# AmpSSM2019_2312.net
KiCad netlist of a schematic drawn in EAGLE
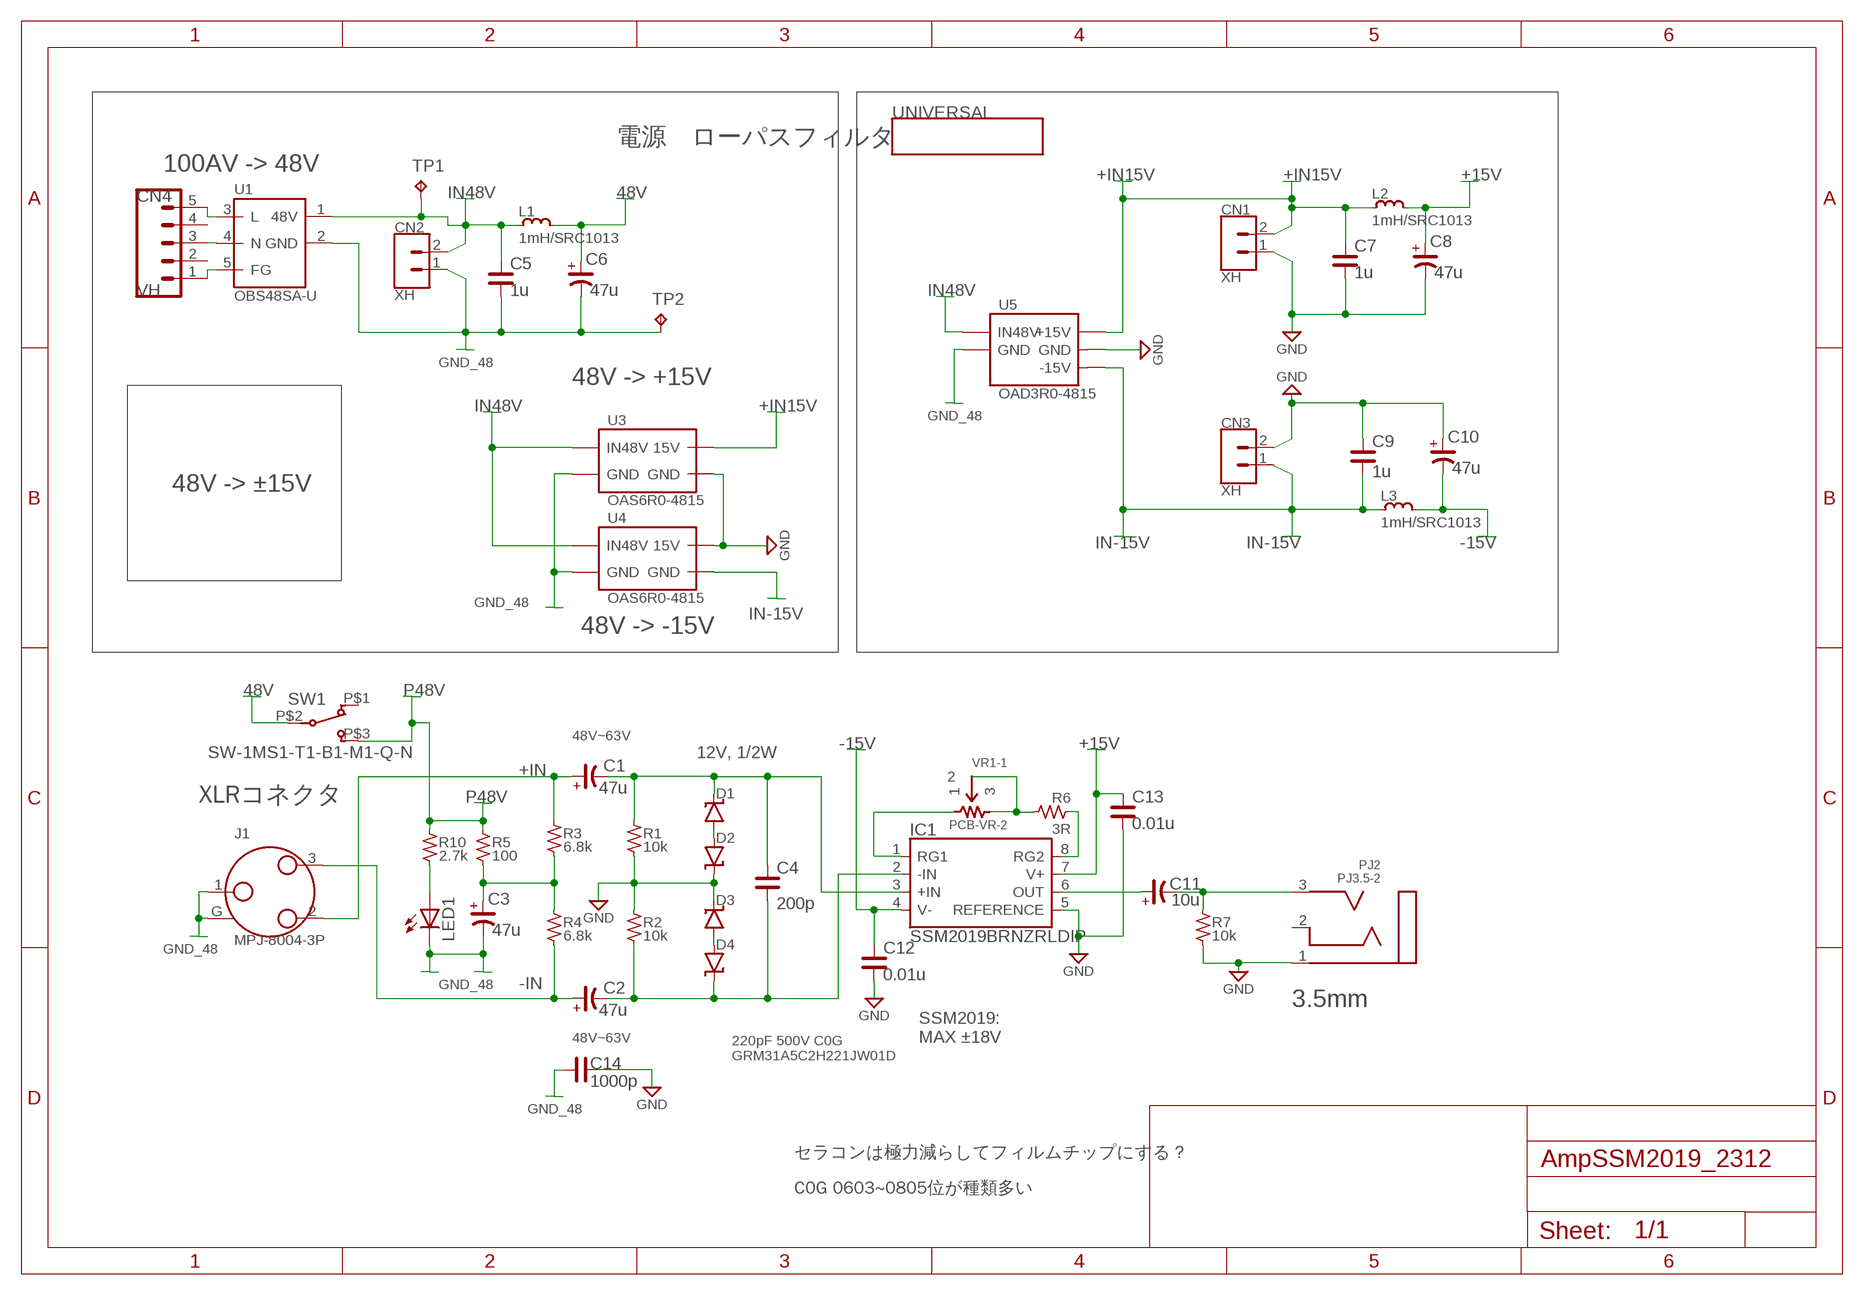
[diagram p0: schematic, sheet 1]

(export (version "E")
  (design (tool "Eeschema 10.0.6"))
  (components
    (comp (ref "C1")
      (value "47u")
      (footprint "eagle-import:CE-025X065")
      (libsource (lib "eagle-import") (part "CP_C025X065"))
    )
    (comp (ref "C2")
      (value "47u")
      (footprint "eagle-import:CE-025X065")
      (libsource (lib "eagle-import") (part "CP_C025X065"))
    )
    (comp (ref "C3")
      (value "47u")
      (footprint "eagle-import:CE-025X065")
      (libsource (lib "eagle-import") (part "CP_C025X065"))
    )
    (comp (ref "C4")
      (value "200p")
      (footprint "eagle-import:C1206")
      (libsource (lib "eagle-import") (part "C_1206"))
    )
    (comp (ref "C5")
      (value "1u")
      (footprint "eagle-import:C1206")
      (libsource (lib "eagle-import") (part "C_1206"))
    )
    (comp (ref "C6")
      (value "47u")
      (footprint "eagle-import:CE-025X065")
      (libsource (lib "eagle-import") (part "CP_C025X065"))
    )
    (comp (ref "C7")
      (value "1u")
      (footprint "eagle-import:C1206")
      (libsource (lib "eagle-import") (part "C_1206"))
    )
    (comp (ref "C8")
      (value "47u")
      (footprint "eagle-import:CE-025X065")
      (libsource (lib "eagle-import") (part "CP_C025X065"))
    )
    (comp (ref "C9")
      (value "1u")
      (footprint "eagle-import:C1206")
      (libsource (lib "eagle-import") (part "C_1206"))
    )
    (comp (ref "C10")
      (value "47u")
      (footprint "eagle-import:CE-025X065")
      (libsource (lib "eagle-import") (part "CP_C025X065"))
    )
    (comp (ref "C11")
      (value "10u")
      (footprint "eagle-import:CE-025X065")
      (libsource (lib "eagle-import") (part "CP_C025X065"))
    )
    (comp (ref "C12")
      (value "0.01u")
      (footprint "eagle-import:C0603")
      (libsource (lib "eagle-import") (part "C_0603"))
    )
    (comp (ref "C13")
      (value "0.01u")
      (footprint "eagle-import:C0603")
      (libsource (lib "eagle-import") (part "C_0603"))
    )
    (comp (ref "C14")
      (value "1000p")
      (footprint "eagle-import:C1206")
      (libsource (lib "eagle-import") (part "C_1206"))
    )
    (comp (ref "CN1")
      (value "XH")
      (footprint "eagle-import:B2B-XH-A")
      (libsource (lib "eagle-import") (part "CN-B2B-XH-A"))
    )
    (comp (ref "CN2")
      (value "XH")
      (footprint "eagle-import:B2B-XH-A")
      (libsource (lib "eagle-import") (part "CN-B2B-XH-A"))
    )
    (comp (ref "CN3")
      (value "XH")
      (footprint "eagle-import:B2B-XH-A")
      (libsource (lib "eagle-import") (part "CN-B2B-XH-A"))
    )
    (comp (ref "CN4")
      (value "VH")
      (footprint "eagle-import:VH5")
      (libsource (lib "eagle-import") (part "M05VH"))
    )
    (comp (ref "D1")
      (value "ZD323")
      (footprint "eagle-import:SOD-323")
      (libsource (lib "eagle-import") (part "ZD323"))
    )
    (comp (ref "D2")
      (value "ZD323")
      (footprint "eagle-import:SOD-323")
      (libsource (lib "eagle-import") (part "ZD323"))
    )
    (comp (ref "D3")
      (value "ZD323")
      (footprint "eagle-import:SOD-323")
      (libsource (lib "eagle-import") (part "ZD323"))
    )
    (comp (ref "D4")
      (value "ZD323")
      (footprint "eagle-import:SOD-323")
      (libsource (lib "eagle-import") (part "ZD323"))
    )
    (comp (ref "IC1")
      (value "SSM2019BRNZRLDIP")
      (footprint "eagle-import:DIL08")
      (libsource (lib "eagle-import") (part "SSM2019BRNZRLDIP"))
    )
    (comp (ref "J1")
      (value "MPJ-8004-3P")
      (footprint "eagle-import:MPJ-8004-3P")
      (libsource (lib "eagle-import") (part "MPJ-8004-3P"))
    )
    (comp (ref "L1")
      (value "1mH/SRC1013")
      (footprint "eagle-import:L13X15")
      (libsource (lib "eagle-import") (part "L_13X15"))
    )
    (comp (ref "L2")
      (value "1mH/SRC1013")
      (footprint "eagle-import:L13X15")
      (libsource (lib "eagle-import") (part "L_13X15"))
    )
    (comp (ref "L3")
      (value "1mH/SRC1013")
      (footprint "eagle-import:L13X15")
      (libsource (lib "eagle-import") (part "L_13X15"))
    )
    (comp (ref "LED1")
      (value "LED3MM")
      (footprint "eagle-import:LED3MM")
      (libsource (lib "eagle-import") (part "LED3MM"))
    )
    (comp (ref "PJ2")
      (value "PJ3.5-2")
      (footprint "eagle-import:PJ3.5-2")
      (libsource (lib "eagle-import") (part "PJ3.5-2"))
    )
    (comp (ref "R1")
      (value "10k")
      (footprint "eagle-import:R0603")
      (libsource (lib "eagle-import") (part "R_0603"))
    )
    (comp (ref "R2")
      (value "10k")
      (footprint "eagle-import:R0603")
      (libsource (lib "eagle-import") (part "R_0603"))
    )
    (comp (ref "R3")
      (value "6.8k")
      (footprint "eagle-import:R0603")
      (libsource (lib "eagle-import") (part "R_0603"))
    )
    (comp (ref "R4")
      (value "6.8k")
      (footprint "eagle-import:R0603")
      (libsource (lib "eagle-import") (part "R_0603"))
    )
    (comp (ref "R5")
      (value "100")
      (footprint "eagle-import:R0603")
      (libsource (lib "eagle-import") (part "R_0603"))
    )
    (comp (ref "R6")
      (value "3R")
      (footprint "eagle-import:R0603")
      (libsource (lib "eagle-import") (part "R_0603"))
    )
    (comp (ref "R7")
      (value "10k")
      (footprint "eagle-import:R0603")
      (libsource (lib "eagle-import") (part "R_0603"))
    )
    (comp (ref "R10")
      (value "2.7k")
      (footprint "eagle-import:R0603")
      (libsource (lib "eagle-import") (part "R_0603"))
    )
    (comp (ref "SW1")
      (value "SW-1MS1-T1-B1-M1-Q-N")
      (footprint "eagle-import:1MS1-T1-B1-M1-Q-N")
      (libsource (lib "eagle-import") (part "SW-1MS1-T1-B1-M1-Q-N"))
    )
    (comp (ref "TP1")
      (value "TPPAD1-13")
      (footprint "eagle-import:P1-13")
      (libsource (lib "eagle-import") (part "TPPAD1-13"))
    )
    (comp (ref "TP2")
      (value "TPPAD1-13")
      (footprint "eagle-import:P1-13")
      (libsource (lib "eagle-import") (part "TPPAD1-13"))
    )
    (comp (ref "U1")
      (value "OBS48SA-U")
      (footprint "eagle-import:OBS48SA-U")
      (libsource (lib "eagle-import") (part "OBS48SA-U"))
    )
    (comp (ref "U2")
      (value "UNIVERSAL10X10")
      (footprint "eagle-import:UNIVERSAL10X10")
      (libsource (lib "eagle-import") (part "UNIVERSAL10X10"))
    )
    (comp (ref "U3")
      (value "OAS6R0-4815")
      (footprint "eagle-import:OAS6R0-4815")
      (libsource (lib "eagle-import") (part "OAS6R0-4815"))
    )
    (comp (ref "U4")
      (value "OAS6R0-4815")
      (footprint "eagle-import:OAS6R0-4815")
      (libsource (lib "eagle-import") (part "OAS6R0-4815"))
    )
    (comp (ref "U5")
      (value "OAD3R0-4815")
      (footprint "eagle-import:OAD3R0-4815")
      (libsource (lib "eagle-import") (part "OAD3R0-4815"))
    )
    (comp (ref "VR1")
      (value "PCB-VR-2")
      (footprint "eagle-import:PCB-VR-2")
      (libsource (lib "eagle-import") (part "PCB-VR-2"))
    )
  )
  (nets
    (net (code "1") (name "/+15V") (class "Default")
      (node (ref "C13") (pin "2") (pinfunction "2_2") (pintype "passive"))
      (node (ref "C8") (pin "+") (pinfunction "+_+") (pintype "passive"))
      (node (ref "IC1") (pin "7") (pinfunction "V+_7") (pintype "bidirectional"))
      (node (ref "L2") (pin "2") (pinfunction "2_2") (pintype "passive"))
    )
    (net (code "2") (name "/+IN") (class "Default")
      (node (ref "C1") (pin "+") (pinfunction "+_+") (pintype "passive"))
      (node (ref "J1") (pin "2") (pinfunction "2_2") (pintype "bidirectional"))
      (node (ref "R3") (pin "2") (pinfunction "2_2") (pintype "passive"))
    )
    (net (code "3") (name "/+IN15V") (class "Default")
      (node (ref "C7") (pin "2") (pinfunction "2_2") (pintype "passive"))
      (node (ref "CN1") (pin "2") (pinfunction "2_2") (pintype "passive"))
      (node (ref "L2") (pin "1") (pinfunction "1_1") (pintype "passive"))
      (node (ref "U3") (pin "V_OUT") (pinfunction "15V_V_OUT") (pintype "bidirectional"))
      (node (ref "U5") (pin "V+_OUT") (pinfunction "+15V_V+_OUT") (pintype "bidirectional"))
    )
    (net (code "4") (name "/-15V") (class "Default")
      (node (ref "C10") (pin "-") (pinfunction "-_-") (pintype "passive"))
      (node (ref "C12") (pin "2") (pinfunction "2_2") (pintype "passive"))
      (node (ref "IC1") (pin "4") (pinfunction "V-_4") (pintype "bidirectional"))
      (node (ref "L3") (pin "2") (pinfunction "2_2") (pintype "passive"))
    )
    (net (code "5") (name "/-IN") (class "Default")
      (node (ref "C2") (pin "+") (pinfunction "+_+") (pintype "passive"))
      (node (ref "J1") (pin "3") (pinfunction "3_3") (pintype "bidirectional"))
      (node (ref "R4") (pin "1") (pinfunction "1_1") (pintype "passive"))
    )
    (net (code "6") (name "/48V") (class "Default")
      (node (ref "C6") (pin "+") (pinfunction "+_+") (pintype "passive"))
      (node (ref "L1") (pin "2") (pinfunction "2_2") (pintype "passive"))
      (node (ref "SW1") (pin "P$2") (pinfunction "P_P$2") (pintype "passive"))
    )
    (net (code "7") (name "/GND_48") (class "Default")
      (node (ref "C14") (pin "2") (pinfunction "2_2") (pintype "passive"))
      (node (ref "C3") (pin "-") (pinfunction "-_-") (pintype "passive"))
      (node (ref "C5") (pin "1") (pinfunction "1_1") (pintype "passive"))
      (node (ref "C6") (pin "-") (pinfunction "-_-") (pintype "passive"))
      (node (ref "CN2") (pin "1") (pinfunction "1_1") (pintype "passive"))
      (node (ref "J1") (pin "1") (pinfunction "1_1") (pintype "bidirectional"))
      (node (ref "J1") (pin "G") (pinfunction "G_G") (pintype "bidirectional"))
      (node (ref "LED1") (pin "K") (pinfunction "C_K") (pintype "passive"))
      (node (ref "TP2") (pin "TP") (pinfunction "TP_TP") (pintype "input"))
      (node (ref "U1") (pin "2") (pinfunction "GND_2") (pintype "bidirectional"))
      (node (ref "U3") (pin "G_IN") (pinfunction "GND_G_IN") (pintype "bidirectional"))
      (node (ref "U4") (pin "G_IN") (pinfunction "GND_G_IN") (pintype "bidirectional"))
      (node (ref "U5") (pin "G_IN") (pinfunction "GND_G_IN") (pintype "bidirectional"))
    )
    (net (code "8") (name "/IN-15V") (class "Default")
      (node (ref "C9") (pin "2") (pinfunction "2_2") (pintype "passive"))
      (node (ref "CN3") (pin "1") (pinfunction "1_1") (pintype "passive"))
      (node (ref "L3") (pin "1") (pinfunction "1_1") (pintype "passive"))
      (node (ref "U4") (pin "G_OUT") (pinfunction "GND_G_OUT") (pintype "bidirectional"))
      (node (ref "U5") (pin "V-_OUT") (pinfunction "-15V_V-_OUT") (pintype "bidirectional"))
    )
    (net (code "9") (name "/IN48V") (class "Default")
      (node (ref "C5") (pin "2") (pinfunction "2_2") (pintype "passive"))
      (node (ref "CN2") (pin "2") (pinfunction "2_2") (pintype "passive"))
      (node (ref "L1") (pin "1") (pinfunction "1_1") (pintype "passive"))
      (node (ref "TP1") (pin "TP") (pinfunction "TP_TP") (pintype "input"))
      (node (ref "U1") (pin "1") (pinfunction "48V_1") (pintype "bidirectional"))
      (node (ref "U3") (pin "VIN") (pinfunction "IN48V_VIN") (pintype "bidirectional"))
      (node (ref "U4") (pin "VIN") (pinfunction "IN48V_VIN") (pintype "bidirectional"))
      (node (ref "U5") (pin "VIN") (pinfunction "IN48V_VIN") (pintype "bidirectional"))
    )
    (net (code "10") (name "/P48V") (class "Default")
      (node (ref "R10") (pin "2") (pinfunction "2_2") (pintype "passive"))
      (node (ref "R5") (pin "2") (pinfunction "2_2") (pintype "passive"))
      (node (ref "SW1") (pin "P$3") (pinfunction "S_P$3") (pintype "passive"))
    )
    (net (code "11") (name "G") (class "Default")
      (node (ref "C10") (pin "+") (pinfunction "+_+") (pintype "passive"))
      (node (ref "C12") (pin "1") (pinfunction "1_1") (pintype "passive"))
      (node (ref "C13") (pin "1") (pinfunction "1_1") (pintype "passive"))
      (node (ref "C14") (pin "1") (pinfunction "1_1") (pintype "passive"))
      (node (ref "C7") (pin "1") (pinfunction "1_1") (pintype "passive"))
      (node (ref "C8") (pin "-") (pinfunction "-_-") (pintype "passive"))
      (node (ref "C9") (pin "1") (pinfunction "1_1") (pintype "passive"))
      (node (ref "CN1") (pin "1") (pinfunction "1_1") (pintype "passive"))
      (node (ref "CN3") (pin "2") (pinfunction "2_2") (pintype "passive"))
      (node (ref "D2") (pin "K") (pinfunction "C_K") (pintype "passive"))
      (node (ref "D3") (pin "K") (pinfunction "C_K") (pintype "passive"))
      (node (ref "IC1") (pin "5") (pinfunction "REFERENCE_5") (pintype "bidirectional"))
      (node (ref "PJ2") (pin "1") (pinfunction "S_1") (pintype "passive"))
      (node (ref "R1") (pin "1") (pinfunction "1_1") (pintype "passive"))
      (node (ref "R2") (pin "2") (pinfunction "2_2") (pintype "passive"))
      (node (ref "R7") (pin "1") (pinfunction "1_1") (pintype "passive"))
      (node (ref "U3") (pin "G_OUT") (pinfunction "GND_G_OUT") (pintype "bidirectional"))
      (node (ref "U4") (pin "V_OUT") (pinfunction "15V_V_OUT") (pintype "bidirectional"))
      (node (ref "U5") (pin "G_OUT") (pinfunction "GND_G_OUT") (pintype "bidirectional"))
    )
    (net (code "12") (name "Net-(C3-Pad+)") (class "Default")
      (node (ref "C3") (pin "+") (pinfunction "+_+") (pintype "passive"))
      (node (ref "R3") (pin "1") (pinfunction "1_1") (pintype "passive"))
      (node (ref "R4") (pin "2") (pinfunction "2_2") (pintype "passive"))
      (node (ref "R5") (pin "1") (pinfunction "1_1") (pintype "passive"))
    )
    (net (code "13") (name "Net-(D1-C)") (class "Default")
      (node (ref "C1") (pin "-") (pinfunction "-_-") (pintype "passive"))
      (node (ref "C4") (pin "2") (pinfunction "2_2") (pintype "passive"))
      (node (ref "D1") (pin "K") (pinfunction "C_K") (pintype "passive"))
      (node (ref "IC1") (pin "3") (pinfunction "+IN_3") (pintype "bidirectional"))
      (node (ref "R1") (pin "2") (pinfunction "2_2") (pintype "passive"))
    )
    (net (code "14") (name "Net-(D1-PadA)") (class "Default")
      (node (ref "D1") (pin "A") (pinfunction "A_A") (pintype "passive"))
      (node (ref "D2") (pin "A") (pinfunction "A_A") (pintype "passive"))
    )
    (net (code "15") (name "Net-(D3-PadA)") (class "Default")
      (node (ref "D3") (pin "A") (pinfunction "A_A") (pintype "passive"))
      (node (ref "D4") (pin "A") (pinfunction "A_A") (pintype "passive"))
    )
    (net (code "16") (name "Net-(D4-C)") (class "Default")
      (node (ref "C2") (pin "-") (pinfunction "-_-") (pintype "passive"))
      (node (ref "C4") (pin "1") (pinfunction "1_1") (pintype "passive"))
      (node (ref "D4") (pin "K") (pinfunction "C_K") (pintype "passive"))
      (node (ref "IC1") (pin "2") (pinfunction "-IN_2") (pintype "bidirectional"))
      (node (ref "R2") (pin "1") (pinfunction "1_1") (pintype "passive"))
    )
    (net (code "17") (name "Net-(IC1-OUT)") (class "Default")
      (node (ref "C11") (pin "+") (pinfunction "+_+") (pintype "passive"))
      (node (ref "IC1") (pin "6") (pinfunction "OUT_6") (pintype "bidirectional"))
    )
    (net (code "18") (name "Net-(IC1-RG1)") (class "Default")
      (node (ref "IC1") (pin "1") (pinfunction "RG1_1") (pintype "bidirectional"))
      (node (ref "VR1") (pin "3") (pinfunction "1_3") (pintype "passive"))
    )
    (net (code "19") (name "Net-(IC1-RG2)") (class "Default")
      (node (ref "IC1") (pin "8") (pinfunction "RG2_8") (pintype "bidirectional"))
      (node (ref "R6") (pin "1") (pinfunction "1_1") (pintype "passive"))
    )
    (net (code "20") (name "Net-(LED1-PadA)") (class "Default")
      (node (ref "LED1") (pin "A") (pinfunction "A_A") (pintype "passive"))
      (node (ref "R10") (pin "1") (pinfunction "1_1") (pintype "passive"))
    )
    (net (code "21") (name "Net-(PJ2-TIP)") (class "Default")
      (node (ref "C11") (pin "-") (pinfunction "-_-") (pintype "passive"))
      (node (ref "PJ2") (pin "3") (pinfunction "TIP_3") (pintype "passive"))
      (node (ref "R7") (pin "2") (pinfunction "2_2") (pintype "passive"))
    )
    (net (code "22") (name "Net-(U1-FG)") (class "Default")
      (node (ref "CN4") (pin "1") (pinfunction "1_1") (pintype "passive"))
      (node (ref "U1") (pin "5") (pinfunction "FG_5") (pintype "bidirectional"))
    )
    (net (code "23") (name "Net-(U1-L)") (class "Default")
      (node (ref "CN4") (pin "5") (pinfunction "5_5") (pintype "passive"))
      (node (ref "U1") (pin "3") (pinfunction "L_3") (pintype "bidirectional"))
    )
    (net (code "24") (name "Net-(U1-N)") (class "Default")
      (node (ref "CN4") (pin "3") (pinfunction "3_3") (pintype "passive"))
      (node (ref "U1") (pin "4") (pinfunction "N_4") (pintype "bidirectional"))
    )
    (net (code "25") (name "Net-(VR1A-3)") (class "Default")
      (node (ref "R6") (pin "2") (pinfunction "2_2") (pintype "passive"))
      (node (ref "VR1") (pin "1") (pinfunction "3_1") (pintype "passive"))
      (node (ref "VR1") (pin "2") (pinfunction "2_2") (pintype "passive"))
    )
    (net (code "26") (name "unconnected-(CN4-Pad2)") (class "Default")
      (node (ref "CN4") (pin "2") (pinfunction "2_2") (pintype "passive"))
    )
    (net (code "27") (name "unconnected-(CN4-Pad4)") (class "Default")
      (node (ref "CN4") (pin "4") (pinfunction "4_4") (pintype "passive"))
    )
    (net (code "28") (name "unconnected-(PJ2-RING-Pad2)") (class "Default")
      (node (ref "PJ2") (pin "2") (pinfunction "RING_2") (pintype "passive"))
    )
    (net (code "29") (name "unconnected-(SW1-O-PadP$1)") (class "Default")
      (node (ref "SW1") (pin "P$1") (pinfunction "O_P$1") (pintype "passive"))
    )
  )
)
